# output_driver.net
KiCad netlist of a schematic drawn in Altium Designer
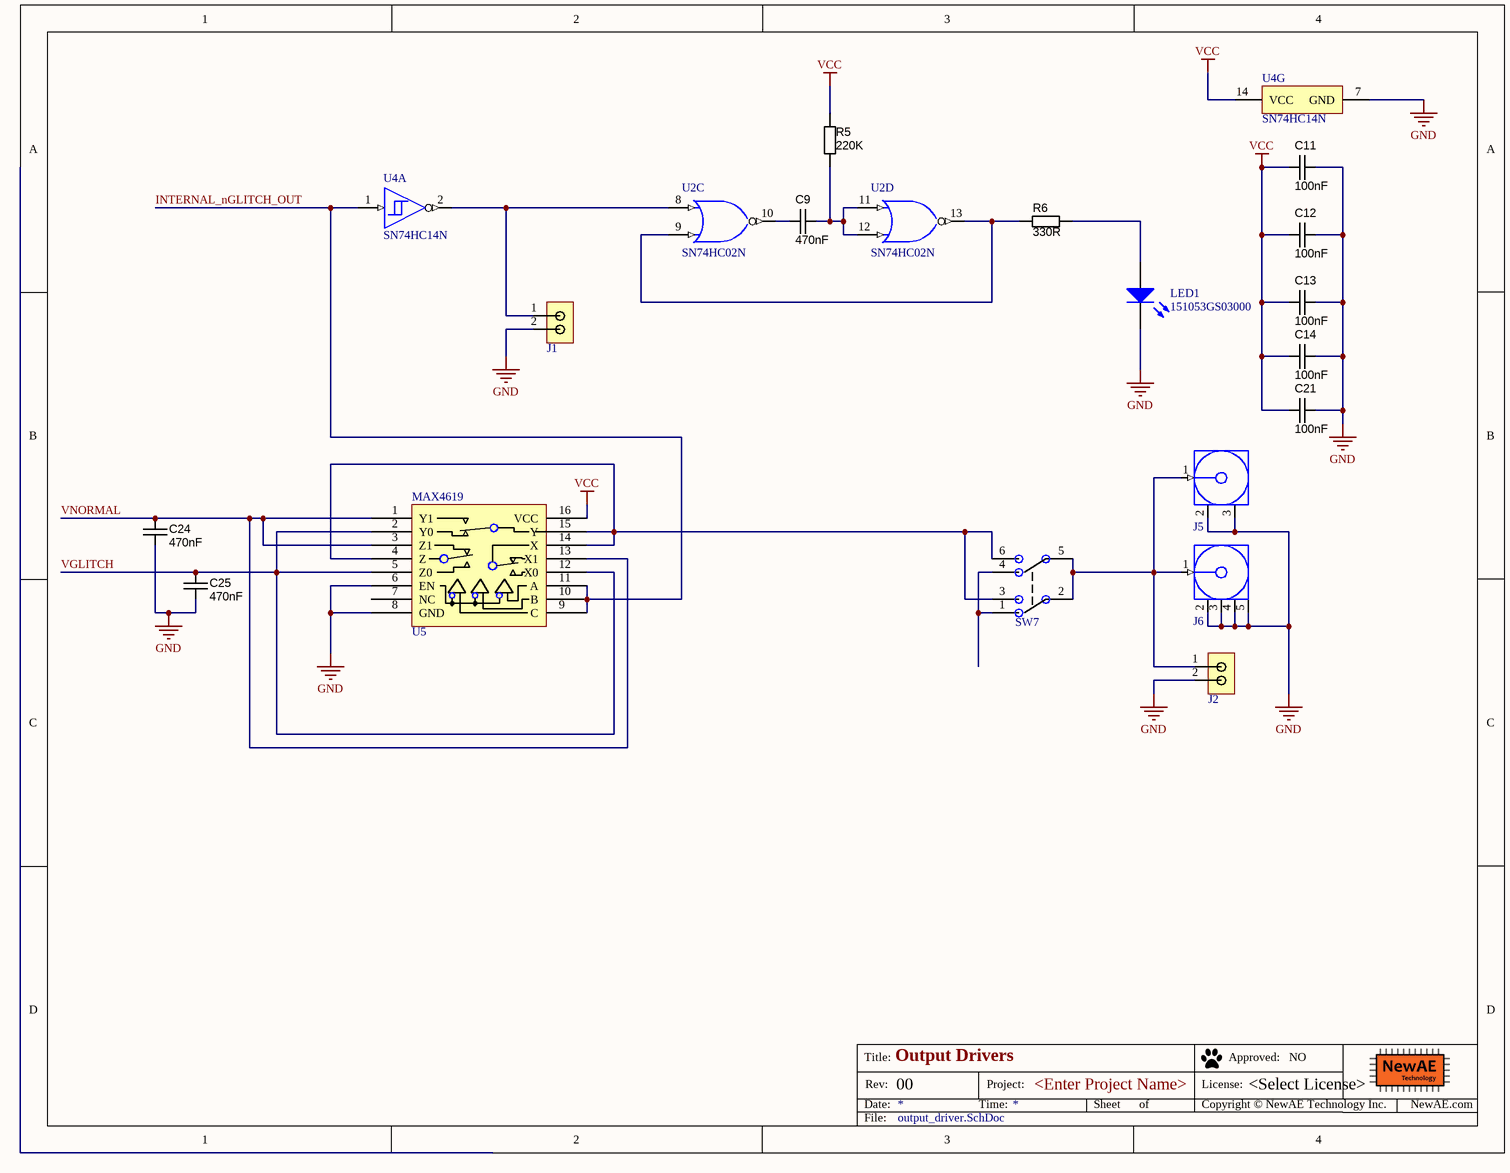
[diagram p0: output_driver.SchDoc]

(export (version "E")
  (design (tool "Eeschema 10.0.6"))
  (components
    (comp (ref "C9")
      (value "470nF")
      (footprint "CAPC500P450250X550")
      (description "Capacitor Ceramic 100nF 10% 50V X7R radial 5mm lead spacing")
      (fields (field (name "TOLERANCE") "±10%") (field (name "Comment") "approved sub OK"))
      (libsource (lib "PBL - Capacitors") (part "CAPR_220n_Radial_5mm"))
    )
    (comp (ref "C11")
      (value "100nF")
      (footprint "CAPC500P450250X550")
      (description "Capacitor Ceramic 220nF 10% 50V X7R radial 5mm lead spacing")
      (fields (field (name "TOLERANCE") "±10%") (field (name "Comment") "approved sub OK"))
      (libsource (lib "PBL - Capacitors") (part "CAPR_220n_Radial_5mm"))
    )
    (comp (ref "C12")
      (value "100nF")
      (footprint "CAPC500P450250X550")
      (description "Capacitor Ceramic 220nF 10% 50V X7R radial 5mm lead spacing")
      (fields (field (name "TOLERANCE") "±10%") (field (name "Comment") "approved sub OK"))
      (libsource (lib "PBL - Capacitors") (part "CAPR_220n_Radial_5mm"))
    )
    (comp (ref "C13")
      (value "100nF")
      (footprint "CAPC500P450250X550")
      (description "Capacitor Ceramic 220nF 10% 50V X7R radial 5mm lead spacing")
      (fields (field (name "TOLERANCE") "±10%") (field (name "Comment") "approved sub OK"))
      (libsource (lib "PBL - Capacitors") (part "CAPR_220n_Radial_5mm"))
    )
    (comp (ref "C14")
      (value "100nF")
      (footprint "CAPC500P450250X550")
      (description "Capacitor Ceramic 220nF 10% 50V X7R radial 5mm lead spacing")
      (fields (field (name "TOLERANCE") "±10%") (field (name "Comment") "approved sub OK"))
      (libsource (lib "PBL - Capacitors") (part "CAPR_220n_Radial_5mm"))
    )
    (comp (ref "C21")
      (value "100nF")
      (footprint "CAPC500P450250X550")
      (description "Capacitor Ceramic 220nF 10% 50V X7R radial 5mm lead spacing")
      (fields (field (name "TOLERANCE") "±10%") (field (name "Comment") "approved sub OK"))
      (libsource (lib "PBL - Capacitors") (part "CAPR_220n_Radial_5mm"))
    )
    (comp (ref "C24")
      (value "470nF")
      (footprint "CAPC500P450250X550")
      (description "Capacitor Ceramic 100nF 10% 50V X7R radial 5mm lead spacing")
      (fields (field (name "TOLERANCE") "±10%") (field (name "Comment") "approved sub OK"))
      (libsource (lib "PBL - Capacitors") (part "CAPR_220n_Radial_5mm"))
    )
    (comp (ref "C25")
      (value "470nF")
      (footprint "CAPC500P450250X550")
      (description "Capacitor Ceramic 100nF 10% 50V X7R radial 5mm lead spacing")
      (fields (field (name "TOLERANCE") "±10%") (field (name "Comment") "approved sub OK"))
      (libsource (lib "PBL - Capacitors") (part "CAPR_220n_Radial_5mm"))
    )
    (comp (ref "J1")
      (value "Jumper")
      (footprint "2x2.54mm_Header")
      (description "1x2 2.54mm header, male pins")
      (fields (field (name "PART NUMBER") "2_PIN_JUMPER"))
      (libsource (lib "NewAE_AltiumLib") (part "1x2_Pin_Header"))
    )
    (comp (ref "J2")
      (value "Jumper")
      (footprint "2x2.54mm_Header")
      (description "1x2 2.54mm header, male pins")
      (fields (field (name "PART NUMBER") "2_PIN_JUMPER"))
      (libsource (lib "NewAE_AltiumLib") (part "1x2_Pin_Header"))
    )
    (comp (ref "J5")
      (value "73171-3150")
      (footprint "73171-3150")
      (description "Molex Cheap R/A BNC")
      (fields (field (name "PART NUMBER") "CON-BNC-CHEAP"))
      (libsource (lib "NewAE_AltiumLib") (part "CON-RF-2GND"))
    )
    (comp (ref "J6")
      (value "CON-SMA-PCBEDGE-003.062")
      (footprint "CON-SMAM-PCB-EDGE062")
      (description "SMA Female Edge Mount Connector for 0.062\" Thick Board")
      (libsource (lib "NewAE_AltiumLib") (part "CON-SMA-PCBEDGE-003.062"))
    )
    (comp (ref "LED1")
      (value "151053GS03000")
      (footprint "Type 5mm")
      (description "THT LED round mono-color waterclear, WL-TMRW, Green")
      (fields (field (name "MANUFACTURER") "Wuerth Elektronik"))
      (libsource (lib "Altium Content Vault") (part "WE-LED_K1A2-2"))
    )
    (comp (ref "R5")
      (value "220K")
      (footprint "RESTH_AXIAL-0.4")
      (description "Resistor THD Axial 10K Ohm 0.25W 5% Carbon Film")
      (fields (field (name "TOLERANCE") "±5%") (field (name "Comment") "Carbon Film"))
      (libsource (lib "") (part "RES_220R_Axial_0.25W_5%_1"))
    )
    (comp (ref "R6")
      (value "330R")
      (footprint "RESTH_AXIAL-0.4")
      (description "Resistor THD Axial 10K Ohm 0.25W 5% Carbon Film")
      (fields (field (name "TOLERANCE") "±5%") (field (name "Comment") "Carbon Film"))
      (libsource (lib "PBL - Resistors") (part "RES_220R_Axial_0.25W_5%"))
    )
    (comp (ref "SW7")
      (value "EG2207")
      (footprint "EG2207")
      (description "DPDT Switch with 2 MH")
      (libsource (lib "NewAE_AltiumLib") (part "SW_DPDT_2MH"))
    )
    (comp (ref "U2")
      (value "SN74HC02N")
      (footprint "N0014A")
      (description "Quadruple 2-Input Positive-NOR Gates, N0014A, TUBE")
      (fields
        (field (name "MANUFACTURER") "Texas Instruments")
        (field (name "GENERIC PART NUMBER") "SN74HC02")
      )
      (libsource (lib "Altium Content Vault") (part "TI-NOR-4-2IN-14"))
    )
    (comp (ref "U4")
      (value "SN74HC14N")
      (footprint "N0014A")
      (description "Hex Schmitt-Trigger Inverters, N0014A, TUBE")
      (fields
        (field (name "MANUFACTURER") "Texas Instruments")
        (field (name "GENERIC PART NUMBER") "SN74HC14")
      )
      (libsource (lib "Altium Content Vault") (part "TI-CD_SNX4XXXXXX4X_19A-14-SCHMITT"))
    )
    (comp (ref "U5")
      (value "MAX4619")
      (footprint "DIP16")
      (description "Analog Mux")
      (libsource (lib "NewAE_AltiumLib") (part "MAX4619"))
    )
  )
  (nets
    (net (code "1") (name "/INTERNAL_nGLITCH_OUT") (class "Default")
      (node (ref "U4") (pin "1") (pinfunction "1A_1") (pintype "input"))
      (node (ref "U5") (pin "10") (pinfunction "B_10") (pintype "passive"))
      (node (ref "U5") (pin "11") (pinfunction "A_11") (pintype "passive"))
      (node (ref "U5") (pin "9") (pinfunction "C_9") (pintype "passive"))
    )
    (net (code "2") (name "/VGLITCH") (class "Default")
      (node (ref "C25") (pin "2") (pintype "passive"))
      (node (ref "U5") (pin "12") (pinfunction "X0_12") (pintype "passive"))
      (node (ref "U5") (pin "2") (pinfunction "Y0_2") (pintype "passive"))
      (node (ref "U5") (pin "5") (pinfunction "Z0_5") (pintype "passive"))
    )
    (net (code "3") (name "/VNORMAL") (class "Default")
      (node (ref "C24") (pin "2") (pintype "passive"))
      (node (ref "U5") (pin "1") (pinfunction "Y1_1") (pintype "passive"))
      (node (ref "U5") (pin "13") (pinfunction "X1_13") (pintype "passive"))
      (node (ref "U5") (pin "3") (pinfunction "Z1_3") (pintype "passive"))
    )
    (net (code "4") (name "GND") (class "Default")
      (node (ref "C11") (pin "1") (pintype "passive"))
      (node (ref "C12") (pin "1") (pintype "passive"))
      (node (ref "C13") (pin "1") (pintype "passive"))
      (node (ref "C14") (pin "1") (pintype "passive"))
      (node (ref "C21") (pin "1") (pintype "passive"))
      (node (ref "C24") (pin "1") (pintype "passive"))
      (node (ref "C25") (pin "1") (pintype "passive"))
      (node (ref "J1") (pin "2") (pinfunction "2_2") (pintype "passive"))
      (node (ref "J2") (pin "2") (pinfunction "2_2") (pintype "passive"))
      (node (ref "J5") (pin "2") (pinfunction "GND_2") (pintype "power_in"))
      (node (ref "J5") (pin "3") (pinfunction "GND_3") (pintype "power_in"))
      (node (ref "J6") (pin "2") (pinfunction "GND_2") (pintype "power_in"))
      (node (ref "J6") (pin "3") (pinfunction "GND_3") (pintype "power_in"))
      (node (ref "J6") (pin "4") (pinfunction "GND_4") (pintype "power_in"))
      (node (ref "J6") (pin "5") (pinfunction "GND_5") (pintype "power_in"))
      (node (ref "LED1") (pin "1") (pinfunction "K_1") (pintype "passive"))
      (node (ref "U4") (pin "7") (pinfunction "GND_7") (pintype "power_in"))
      (node (ref "U5") (pin "6") (pinfunction "EN_6") (pintype "passive"))
      (node (ref "U5") (pin "8") (pinfunction "GND_8") (pintype "passive"))
    )
    (net (code "5") (name "Net-(J5-Signal)") (class "Default")
      (node (ref "J2") (pin "1") (pinfunction "1_1") (pintype "passive"))
      (node (ref "J5") (pin "1") (pinfunction "Signal_1") (pintype "input"))
      (node (ref "J6") (pin "1") (pinfunction "Signal_1") (pintype "input"))
      (node (ref "SW7") (pin "2") (pinfunction "IN_2") (pintype "passive"))
      (node (ref "SW7") (pin "5") (pinfunction "IN_5") (pintype "passive"))
    )
    (net (code "6") (name "Net-(LED1-A)") (class "Default")
      (node (ref "LED1") (pin "2") (pinfunction "A_2") (pintype "passive"))
      (node (ref "R6") (pin "1") (pinfunction "1_1") (pintype "passive"))
    )
    (net (code "7") (name "Net-(SW7-IN-Pad1)") (class "Default")
      (node (ref "SW7") (pin "1") (pinfunction "IN_1") (pintype "passive"))
      (node (ref "SW7") (pin "4") (pinfunction "IN_4") (pintype "passive"))
    )
    (net (code "8") (name "Net-(U2C-3A)") (class "Default")
      (node (ref "J1") (pin "1") (pinfunction "1_1") (pintype "passive"))
      (node (ref "U2") (pin "8") (pinfunction "3A_8") (pintype "input"))
      (node (ref "U4") (pin "2") (pinfunction "~{1Y}_2") (pintype "output"))
    )
    (net (code "9") (name "Net-(U2C-3B)") (class "Default")
      (node (ref "R6") (pin "2") (pinfunction "2_2") (pintype "passive"))
      (node (ref "U2") (pin "13") (pinfunction "4Y_13") (pintype "output"))
      (node (ref "U2") (pin "9") (pinfunction "3B_9") (pintype "input"))
    )
    (net (code "10") (name "Net-(U2C-3Y)") (class "Default")
      (node (ref "C9") (pin "1") (pintype "passive"))
      (node (ref "U2") (pin "10") (pinfunction "3Y_10") (pintype "output"))
    )
    (net (code "11") (name "Net-(U2D-4A)") (class "Default")
      (node (ref "C9") (pin "2") (pintype "passive"))
      (node (ref "R5") (pin "1") (pinfunction "1_1") (pintype "passive"))
      (node (ref "U2") (pin "11") (pinfunction "4A_11") (pintype "input"))
      (node (ref "U2") (pin "12") (pinfunction "4B_12") (pintype "input"))
    )
    (net (code "12") (name "Net-(U5-X)") (class "Default")
      (node (ref "SW7") (pin "3") (pinfunction "IN_3") (pintype "passive"))
      (node (ref "SW7") (pin "6") (pinfunction "IN_6") (pintype "passive"))
      (node (ref "U5") (pin "14") (pinfunction "X_14") (pintype "passive"))
      (node (ref "U5") (pin "15") (pinfunction "Y_15") (pintype "passive"))
      (node (ref "U5") (pin "4") (pinfunction "Z_4") (pintype "passive"))
    )
    (net (code "13") (name "VCC") (class "Default")
      (node (ref "C11") (pin "2") (pintype "passive"))
      (node (ref "C12") (pin "2") (pintype "passive"))
      (node (ref "C13") (pin "2") (pintype "passive"))
      (node (ref "C14") (pin "2") (pintype "passive"))
      (node (ref "C21") (pin "2") (pintype "passive"))
      (node (ref "R5") (pin "2") (pinfunction "2_2") (pintype "passive"))
      (node (ref "U4") (pin "14") (pinfunction "VCC_14") (pintype "power_in"))
      (node (ref "U5") (pin "16") (pinfunction "VCC_16") (pintype "passive"))
    )
    (net (code "14") (name "unconnected-(U5-NC-Pad7)") (class "Default")
      (node (ref "U5") (pin "7") (pinfunction "NC_7") (pintype "passive"))
    )
  )
)
